# MesschieberV3.net
KiCad netlist of a schematic drawn in EAGLE
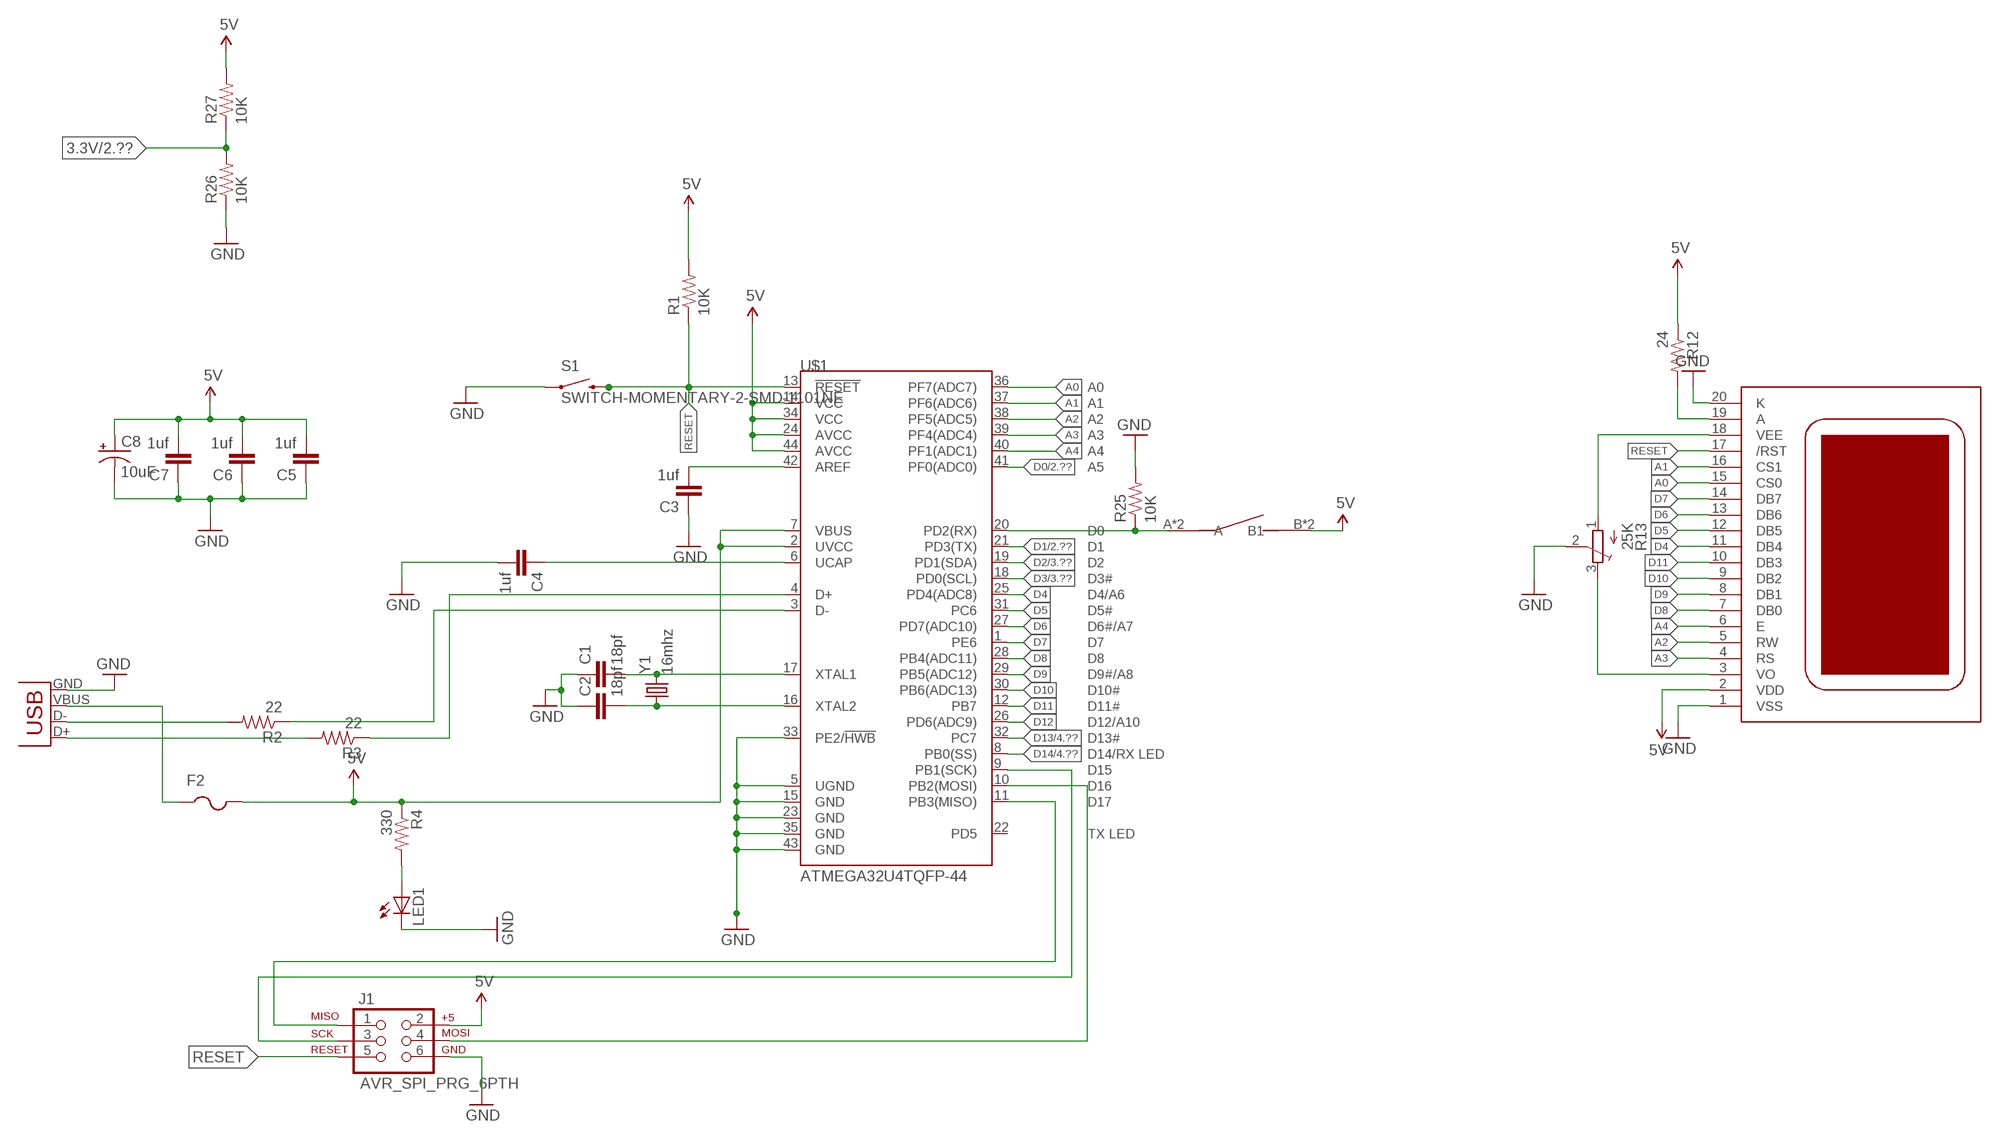
[diagram p0: schematic, sheet 1]
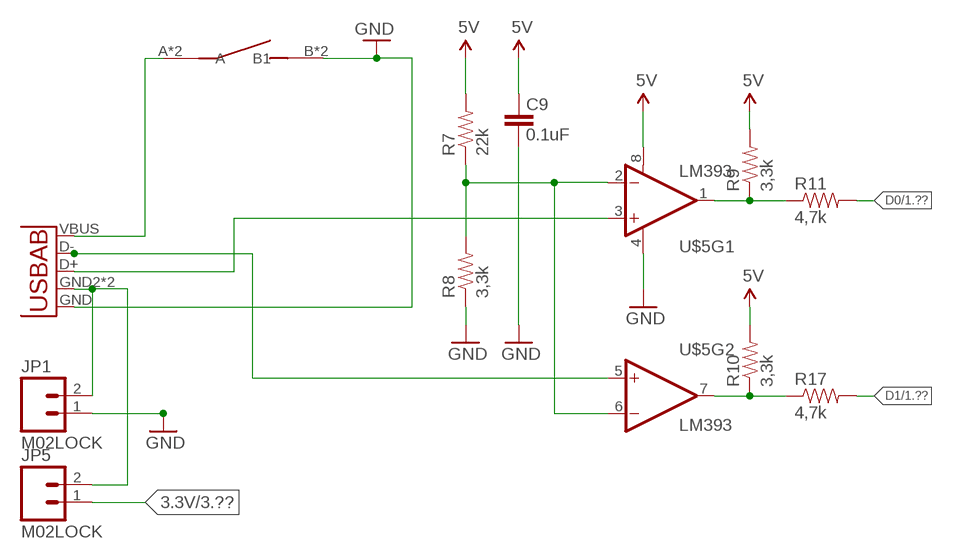
[diagram p1: schematic, sheet 2]
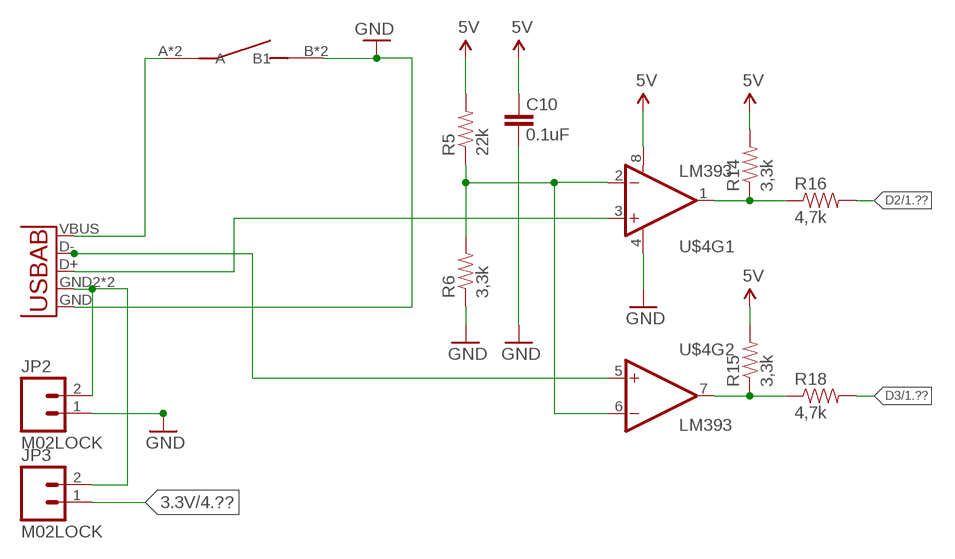
[diagram p2: schematic, sheet 3]
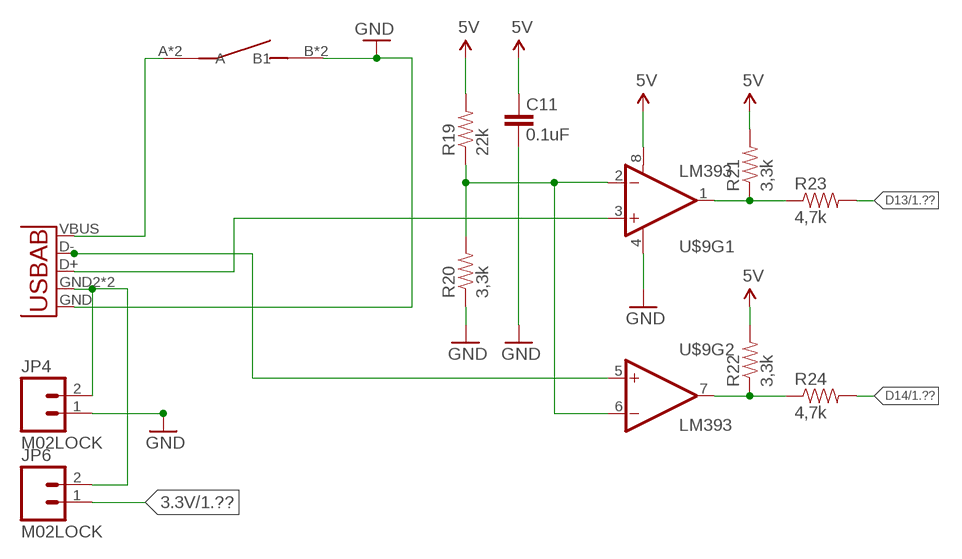
[diagram p3: schematic, sheet 4]

(export (version "E")
  (design (tool "Eeschema 10.0.6"))
  (components
    (comp (ref "C9")
      (value "0.1uF")
      (footprint "eagle-import:0805")
      (libsource (lib "eagle-import") (part "CAP0805"))
    )
    (comp (ref "JP1")
      (value "M02LOCK")
      (footprint "eagle-import:1X02_LOCK")
      (libsource (lib "eagle-import") (part "M02LOCK"))
    )
    (comp (ref "JP5")
      (value "M02LOCK")
      (footprint "eagle-import:1X02_LOCK")
      (libsource (lib "eagle-import") (part "M02LOCK"))
    )
    (comp (ref "R7")
      (value "22k")
      (footprint "eagle-import:0805")
      (libsource (lib "eagle-import") (part "RESISTOR"))
    )
    (comp (ref "R8")
      (value "3,3k")
      (footprint "eagle-import:0805")
      (libsource (lib "eagle-import") (part "RESISTOR"))
    )
    (comp (ref "R9")
      (value "3,3k")
      (footprint "eagle-import:0805")
      (libsource (lib "eagle-import") (part "RESISTOR"))
    )
    (comp (ref "R10")
      (value "3,3k")
      (footprint "eagle-import:0805")
      (libsource (lib "eagle-import") (part "RESISTOR"))
    )
    (comp (ref "R11")
      (value "4,7k")
      (footprint "eagle-import:0805")
      (libsource (lib "eagle-import") (part "RESISTOR"))
    )
    (comp (ref "R17")
      (value "4,7k")
      (footprint "eagle-import:0805")
      (libsource (lib "eagle-import") (part "RESISTOR"))
    )
    (comp (ref "U$3")
      (value "TASTE_R3FTL6")
      (footprint "eagle-import:TASTE_R3FTL6")
      (libsource (lib "eagle-import") (part "TASTE_R3FTL6"))
    )
    (comp (ref "U$5")
      (value "LM393")
      (footprint "eagle-import:SO08")
      (libsource (lib "eagle-import") (part "LM393"))
    )
    (comp (ref "U$7")
      (value "USB-A")
      (footprint "eagle-import:USB-A")
      (libsource (lib "eagle-import") (part "USB-A"))
    )
    (comp (ref "C11")
      (value "0.1uF")
      (footprint "eagle-import:0805")
      (libsource (lib "eagle-import") (part "CAP0805"))
    )
    (comp (ref "JP4")
      (value "M02LOCK")
      (footprint "eagle-import:1X02_LOCK")
      (libsource (lib "eagle-import") (part "M02LOCK"))
    )
    (comp (ref "JP6")
      (value "M02LOCK")
      (footprint "eagle-import:1X02_LOCK")
      (libsource (lib "eagle-import") (part "M02LOCK"))
    )
    (comp (ref "R19")
      (value "22k")
      (footprint "eagle-import:0805")
      (libsource (lib "eagle-import") (part "RESISTOR"))
    )
    (comp (ref "R20")
      (value "3,3k")
      (footprint "eagle-import:0805")
      (libsource (lib "eagle-import") (part "RESISTOR"))
    )
    (comp (ref "R21")
      (value "3,3k")
      (footprint "eagle-import:0805")
      (libsource (lib "eagle-import") (part "RESISTOR"))
    )
    (comp (ref "R22")
      (value "3,3k")
      (footprint "eagle-import:0805")
      (libsource (lib "eagle-import") (part "RESISTOR"))
    )
    (comp (ref "R23")
      (value "4,7k")
      (footprint "eagle-import:0805")
      (libsource (lib "eagle-import") (part "RESISTOR"))
    )
    (comp (ref "R24")
      (value "4,7k")
      (footprint "eagle-import:0805")
      (libsource (lib "eagle-import") (part "RESISTOR"))
    )
    (comp (ref "U$9")
      (value "LM393")
      (footprint "eagle-import:SO08")
      (libsource (lib "eagle-import") (part "LM393"))
    )
    (comp (ref "U$10")
      (value "USB-A")
      (footprint "eagle-import:USB-A")
      (libsource (lib "eagle-import") (part "USB-A"))
    )
    (comp (ref "U$11")
      (value "TASTE_R3FTL6")
      (footprint "eagle-import:TASTE_R3FTL6")
      (libsource (lib "eagle-import") (part "TASTE_R3FTL6"))
    )
    (comp (ref "C10")
      (value "0.1uF")
      (footprint "eagle-import:0805")
      (libsource (lib "eagle-import") (part "CAP0805"))
    )
    (comp (ref "JP2")
      (value "M02LOCK")
      (footprint "eagle-import:1X02_LOCK")
      (libsource (lib "eagle-import") (part "M02LOCK"))
    )
    (comp (ref "JP3")
      (value "M02LOCK")
      (footprint "eagle-import:1X02_LOCK")
      (libsource (lib "eagle-import") (part "M02LOCK"))
    )
    (comp (ref "R5")
      (value "22k")
      (footprint "eagle-import:0805")
      (libsource (lib "eagle-import") (part "RESISTOR"))
    )
    (comp (ref "R6")
      (value "3,3k")
      (footprint "eagle-import:0805")
      (libsource (lib "eagle-import") (part "RESISTOR"))
    )
    (comp (ref "R14")
      (value "3,3k")
      (footprint "eagle-import:0805")
      (libsource (lib "eagle-import") (part "RESISTOR"))
    )
    (comp (ref "R15")
      (value "3,3k")
      (footprint "eagle-import:0805")
      (libsource (lib "eagle-import") (part "RESISTOR"))
    )
    (comp (ref "R16")
      (value "4,7k")
      (footprint "eagle-import:0805")
      (libsource (lib "eagle-import") (part "RESISTOR"))
    )
    (comp (ref "R18")
      (value "4,7k")
      (footprint "eagle-import:0805")
      (libsource (lib "eagle-import") (part "RESISTOR"))
    )
    (comp (ref "U$4")
      (value "LM393")
      (footprint "eagle-import:SO08")
      (libsource (lib "eagle-import") (part "LM393"))
    )
    (comp (ref "U$6")
      (value "USB-A")
      (footprint "eagle-import:USB-A")
      (libsource (lib "eagle-import") (part "USB-A"))
    )
    (comp (ref "U$8")
      (value "TASTE_R3FTL6")
      (footprint "eagle-import:TASTE_R3FTL6")
      (libsource (lib "eagle-import") (part "TASTE_R3FTL6"))
    )
    (comp (ref "C1")
      (value "18pf")
      (footprint "eagle-import:0805")
      (libsource (lib "eagle-import") (part "SparkFun-Capacitors_CAP0805"))
    )
    (comp (ref "C2")
      (value "18pf")
      (footprint "eagle-import:0805")
      (libsource (lib "eagle-import") (part "SparkFun-Capacitors_CAP0805"))
    )
    (comp (ref "C3")
      (value "1uf")
      (footprint "eagle-import:0805")
      (libsource (lib "eagle-import") (part "SparkFun-Capacitors_CAP0805"))
    )
    (comp (ref "C4")
      (value "1uf")
      (footprint "eagle-import:0805")
      (libsource (lib "eagle-import") (part "SparkFun-Capacitors_CAP0805"))
    )
    (comp (ref "C5")
      (value "1uf")
      (footprint "eagle-import:0805")
      (libsource (lib "eagle-import") (part "SparkFun-Capacitors_CAP0805"))
    )
    (comp (ref "C6")
      (value "1uf")
      (footprint "eagle-import:0805")
      (libsource (lib "eagle-import") (part "SparkFun-Capacitors_CAP0805"))
    )
    (comp (ref "C7")
      (value "1uf")
      (footprint "eagle-import:0805")
      (libsource (lib "eagle-import") (part "SparkFun-Capacitors_CAP0805"))
    )
    (comp (ref "C8")
      (value "10uF")
      (footprint "eagle-import:EIA3528")
      (libsource (lib "eagle-import") (part "10UF-20V-10%(TANT)"))
    )
    (comp (ref "F2")
      (value "PTCFUSE-1812")
      (footprint "eagle-import:1812")
      (libsource (lib "eagle-import") (part "PTCFUSE-1812"))
    )
    (comp (ref "J1")
      (value "AVR_SPI_PRG_6PTH")
      (footprint "eagle-import:2X3")
      (libsource (lib "eagle-import") (part "AVR_SPI_PRG_6PTH"))
    )
    (comp (ref "JP7")
      (value "USB-SMD-NS")
      (footprint "eagle-import:USB-MINIB-NOSTOP")
      (libsource (lib "eagle-import") (part "USB-SMD-NS"))
    )
    (comp (ref "LED1")
      (value "LEDSML0805")
      (footprint "eagle-import:SML0805")
      (libsource (lib "eagle-import") (part "LEDSML0805"))
    )
    (comp (ref "R1")
      (value "10K")
      (footprint "eagle-import:0805")
      (libsource (lib "eagle-import") (part "RESISTOR"))
    )
    (comp (ref "R2")
      (value "22")
      (footprint "eagle-import:0805")
      (libsource (lib "eagle-import") (part "RESISTOR"))
    )
    (comp (ref "R3")
      (value "22")
      (footprint "eagle-import:0805")
      (libsource (lib "eagle-import") (part "RESISTOR"))
    )
    (comp (ref "R4")
      (value "330")
      (footprint "eagle-import:0805")
      (libsource (lib "eagle-import") (part "RESISTOR"))
    )
    (comp (ref "R12")
      (value "24")
      (footprint "eagle-import:0805")
      (libsource (lib "eagle-import") (part "RESISTOR"))
    )
    (comp (ref "R13")
      (value "25K")
      (footprint "eagle-import:SM-42_43A")
      (libsource (lib "eagle-import") (part "TRIM_EU-SM-42/43A"))
    )
    (comp (ref "R25")
      (value "10K")
      (footprint "eagle-import:0805")
      (libsource (lib "eagle-import") (part "RESISTOR"))
    )
    (comp (ref "R26")
      (value "10K")
      (footprint "eagle-import:0805")
      (libsource (lib "eagle-import") (part "RESISTOR"))
    )
    (comp (ref "R27")
      (value "10K")
      (footprint "eagle-import:0805")
      (libsource (lib "eagle-import") (part "RESISTOR"))
    )
    (comp (ref "S1")
      (value "SWITCH-MOMENTARY-2-SMD-1101NE")
      (footprint "eagle-import:TACTILE-SWITCH-1101NE")
      (libsource (lib "eagle-import") (part "SWITCH-MOMENTARY-2-SMD-1101NE"))
    )
    (comp (ref "U$1")
      (value "ATMEGA32U4TQFP-44")
      (footprint "eagle-import:TQFP44")
      (libsource (lib "eagle-import") (part "ATMEGA32U4TQFP-44"))
    )
    (comp (ref "U$2")
      (value "TS12864A")
      (footprint "eagle-import:TS12864")
      (libsource (lib "eagle-import") (part "TS12864A"))
    )
    (comp (ref "U$12")
      (value "TASTE_R3FTL6")
      (footprint "eagle-import:TASTE_R3FTL6")
      (libsource (lib "eagle-import") (part "TASTE_R3FTL6"))
    )
    (comp (ref "Y1")
      (value "16mhz")
      (footprint "eagle-import:CRYSTAL-SMD-5X3")
      (libsource (lib "eagle-import") (part "CRYSTAL5X3"))
    )
  )
  (nets
    (net (code "1") (name "3.3V") (class "Default")
      (node (ref "JP3") (pin "1") (pinfunction "1_1") (pintype "passive"))
      (node (ref "JP5") (pin "1") (pinfunction "1_1") (pintype "passive"))
      (node (ref "JP6") (pin "1") (pinfunction "1_1") (pintype "passive"))
      (node (ref "R26") (pin "2") (pinfunction "2_2") (pintype "passive"))
      (node (ref "R27") (pin "1") (pinfunction "1_1") (pintype "passive"))
    )
    (net (code "2") (name "5V") (class "Default")
      (node (ref "C10") (pin "2") (pinfunction "2_2") (pintype "passive"))
      (node (ref "C11") (pin "2") (pinfunction "2_2") (pintype "passive"))
      (node (ref "C5") (pin "2") (pinfunction "2_2") (pintype "passive"))
      (node (ref "C6") (pin "2") (pinfunction "2_2") (pintype "passive"))
      (node (ref "C7") (pin "2") (pinfunction "2_2") (pintype "passive"))
      (node (ref "C8") (pin "A") (pinfunction "+_A") (pintype "passive"))
      (node (ref "C9") (pin "2") (pinfunction "2_2") (pintype "passive"))
      (node (ref "F2") (pin "2") (pinfunction "2_2") (pintype "passive"))
      (node (ref "J1") (pin "2") (pinfunction "2_2") (pintype "passive"))
      (node (ref "R1") (pin "2") (pinfunction "2_2") (pintype "passive"))
      (node (ref "R10") (pin "2") (pinfunction "2_2") (pintype "passive"))
      (node (ref "R12") (pin "1") (pinfunction "1_1") (pintype "passive"))
      (node (ref "R14") (pin "2") (pinfunction "2_2") (pintype "passive"))
      (node (ref "R15") (pin "2") (pinfunction "2_2") (pintype "passive"))
      (node (ref "R19") (pin "2") (pinfunction "2_2") (pintype "passive"))
      (node (ref "R21") (pin "2") (pinfunction "2_2") (pintype "passive"))
      (node (ref "R22") (pin "2") (pinfunction "2_2") (pintype "passive"))
      (node (ref "R27") (pin "2") (pinfunction "2_2") (pintype "passive"))
      (node (ref "R4") (pin "1") (pinfunction "1_1") (pintype "passive"))
      (node (ref "R5") (pin "2") (pinfunction "2_2") (pintype "passive"))
      (node (ref "R7") (pin "2") (pinfunction "2_2") (pintype "passive"))
      (node (ref "R9") (pin "2") (pinfunction "2_2") (pintype "passive"))
      (node (ref "U$1") (pin "14") (pinfunction "VCC_14") (pintype "bidirectional"))
      (node (ref "U$1") (pin "2") (pinfunction "UVCC_2") (pintype "bidirectional"))
      (node (ref "U$1") (pin "24") (pinfunction "AVCC_24") (pintype "bidirectional"))
      (node (ref "U$1") (pin "34") (pinfunction "VCC_34") (pintype "bidirectional"))
      (node (ref "U$1") (pin "44") (pinfunction "AVCC_44") (pintype "bidirectional"))
      (node (ref "U$1") (pin "7") (pinfunction "VBUS_7") (pintype "bidirectional"))
      (node (ref "U$12") (pin "B") (pinfunction "B1_B") (pintype "bidirectional"))
      (node (ref "U$12") (pin "B1") (pinfunction "B1_B1") (pintype "bidirectional"))
      (node (ref "U$2") (pin "2") (pinfunction "VDD_2") (pintype "power_in"))
      (node (ref "U$4") (pin "8") (pinfunction "V+_8") (pintype "power_in"))
      (node (ref "U$5") (pin "8") (pinfunction "V+_8") (pintype "power_in"))
      (node (ref "U$9") (pin "8") (pinfunction "V+_8") (pintype "power_in"))
    )
    (net (code "3") (name "A0") (class "Default")
      (node (ref "U$1") (pin "36") (pinfunction "PF7(ADC7)_36") (pintype "bidirectional"))
      (node (ref "U$2") (pin "15") (pinfunction "CS0_15") (pintype "input"))
    )
    (net (code "4") (name "A1") (class "Default")
      (node (ref "U$1") (pin "37") (pinfunction "PF6(ADC6)_37") (pintype "bidirectional"))
      (node (ref "U$2") (pin "16") (pinfunction "CS1_16") (pintype "input"))
    )
    (net (code "5") (name "A2") (class "Default")
      (node (ref "U$1") (pin "38") (pinfunction "PF5(ADC5)_38") (pintype "bidirectional"))
      (node (ref "U$2") (pin "5") (pinfunction "RW_5") (pintype "input"))
    )
    (net (code "6") (name "A3") (class "Default")
      (node (ref "U$1") (pin "39") (pinfunction "PF4(ADC4)_39") (pintype "bidirectional"))
      (node (ref "U$2") (pin "4") (pinfunction "RS_4") (pintype "input"))
    )
    (net (code "7") (name "A4") (class "Default")
      (node (ref "U$1") (pin "40") (pinfunction "PF1(ADC1)_40") (pintype "bidirectional"))
      (node (ref "U$2") (pin "6") (pinfunction "E_6") (pintype "input"))
    )
    (net (code "8") (name "D0") (class "Default")
      (node (ref "R11") (pin "2") (pinfunction "2_2") (pintype "passive"))
      (node (ref "U$1") (pin "41") (pinfunction "PF0(ADC0)_41") (pintype "bidirectional"))
    )
    (net (code "9") (name "D1") (class "Default")
      (node (ref "R17") (pin "2") (pinfunction "2_2") (pintype "passive"))
      (node (ref "U$1") (pin "21") (pinfunction "PD3(TX)_21") (pintype "bidirectional"))
    )
    (net (code "10") (name "D2") (class "Default")
      (node (ref "R16") (pin "2") (pinfunction "2_2") (pintype "passive"))
      (node (ref "U$1") (pin "19") (pinfunction "PD1(SDA)_19") (pintype "bidirectional"))
    )
    (net (code "11") (name "D3") (class "Default")
      (node (ref "R18") (pin "2") (pinfunction "2_2") (pintype "passive"))
      (node (ref "U$1") (pin "18") (pinfunction "PD0(SCL)_18") (pintype "bidirectional"))
    )
    (net (code "12") (name "D4") (class "Default")
      (node (ref "U$1") (pin "25") (pinfunction "PD4(ADC8)_25") (pintype "bidirectional"))
      (node (ref "U$2") (pin "11") (pinfunction "DB4_11") (pintype "bidirectional"))
    )
    (net (code "13") (name "D5") (class "Default")
      (node (ref "U$1") (pin "31") (pinfunction "PC6_31") (pintype "bidirectional"))
      (node (ref "U$2") (pin "12") (pinfunction "DB5_12") (pintype "bidirectional"))
    )
    (net (code "14") (name "D6") (class "Default")
      (node (ref "U$1") (pin "27") (pinfunction "PD7(ADC10)_27") (pintype "bidirectional"))
      (node (ref "U$2") (pin "13") (pinfunction "DB6_13") (pintype "bidirectional"))
    )
    (net (code "15") (name "D7") (class "Default")
      (node (ref "U$1") (pin "1") (pinfunction "PE6_1") (pintype "bidirectional"))
      (node (ref "U$2") (pin "14") (pinfunction "DB7_14") (pintype "bidirectional"))
    )
    (net (code "16") (name "D8") (class "Default")
      (node (ref "U$1") (pin "28") (pinfunction "PB4(ADC11)_28") (pintype "bidirectional"))
      (node (ref "U$2") (pin "7") (pinfunction "DB0_7") (pintype "bidirectional"))
    )
    (net (code "17") (name "D9") (class "Default")
      (node (ref "U$1") (pin "29") (pinfunction "PB5(ADC12)_29") (pintype "bidirectional"))
      (node (ref "U$2") (pin "8") (pinfunction "DB1_8") (pintype "bidirectional"))
    )
    (net (code "18") (name "D10") (class "Default")
      (node (ref "U$1") (pin "30") (pinfunction "PB6(ADC13)_30") (pintype "bidirectional"))
      (node (ref "U$2") (pin "9") (pinfunction "DB2_9") (pintype "bidirectional"))
    )
    (net (code "19") (name "D11") (class "Default")
      (node (ref "U$1") (pin "12") (pinfunction "PB7_12") (pintype "bidirectional"))
      (node (ref "U$2") (pin "10") (pinfunction "DB3_10") (pintype "bidirectional"))
    )
    (net (code "20") (name "D12") (class "Default")
      (node (ref "U$1") (pin "26") (pinfunction "PD6(ADC9)_26") (pintype "bidirectional"))
    )
    (net (code "21") (name "D13") (class "Default")
      (node (ref "R23") (pin "2") (pinfunction "2_2") (pintype "passive"))
      (node (ref "U$1") (pin "32") (pinfunction "PC7_32") (pintype "bidirectional"))
    )
    (net (code "22") (name "D14") (class "Default")
      (node (ref "R24") (pin "2") (pinfunction "2_2") (pintype "passive"))
      (node (ref "U$1") (pin "8") (pinfunction "PB0(SS)_8") (pintype "bidirectional"))
    )
    (net (code "23") (name "GND") (class "Default")
      (node (ref "C1") (pin "1") (pinfunction "1_1") (pintype "passive"))
      (node (ref "C10") (pin "1") (pinfunction "1_1") (pintype "passive"))
      (node (ref "C11") (pin "1") (pinfunction "1_1") (pintype "passive"))
      (node (ref "C2") (pin "1") (pinfunction "1_1") (pintype "passive"))
      (node (ref "C3") (pin "1") (pinfunction "1_1") (pintype "passive"))
      (node (ref "C4") (pin "2") (pinfunction "2_2") (pintype "passive"))
      (node (ref "C5") (pin "1") (pinfunction "1_1") (pintype "passive"))
      (node (ref "C6") (pin "1") (pinfunction "1_1") (pintype "passive"))
      (node (ref "C7") (pin "1") (pinfunction "1_1") (pintype "passive"))
      (node (ref "C8") (pin "C") (pinfunction "-_C") (pintype "passive"))
      (node (ref "C9") (pin "1") (pinfunction "1_1") (pintype "passive"))
      (node (ref "J1") (pin "6") (pinfunction "6_6") (pintype "passive"))
      (node (ref "JP1") (pin "1") (pinfunction "1_1") (pintype "passive"))
      (node (ref "JP2") (pin "1") (pinfunction "1_1") (pintype "passive"))
      (node (ref "JP4") (pin "1") (pinfunction "1_1") (pintype "passive"))
      (node (ref "JP7") (pin "GND") (pinfunction "GND_GND") (pintype "bidirectional"))
      (node (ref "LED1") (pin "C") (pinfunction "C_C") (pintype "passive"))
      (node (ref "R13") (pin "2") (pinfunction "S_2") (pintype "passive"))
      (node (ref "R20") (pin "1") (pinfunction "1_1") (pintype "passive"))
      (node (ref "R25") (pin "2") (pinfunction "2_2") (pintype "passive"))
      (node (ref "R26") (pin "1") (pinfunction "1_1") (pintype "passive"))
      (node (ref "R6") (pin "1") (pinfunction "1_1") (pintype "passive"))
      (node (ref "R8") (pin "1") (pinfunction "1_1") (pintype "passive"))
      (node (ref "S1") (pin "P$1") (pinfunction "1_P$1") (pintype "passive"))
      (node (ref "U$1") (pin "15") (pinfunction "GND_15") (pintype "bidirectional"))
      (node (ref "U$1") (pin "23") (pinfunction "GND_23") (pintype "bidirectional"))
      (node (ref "U$1") (pin "33") (pinfunction "PE2/~{HWB}_33") (pintype "bidirectional"))
      (node (ref "U$1") (pin "35") (pinfunction "GND_35") (pintype "bidirectional"))
      (node (ref "U$1") (pin "43") (pinfunction "GND_43") (pintype "bidirectional"))
      (node (ref "U$1") (pin "5") (pinfunction "UGND_5") (pintype "bidirectional"))
      (node (ref "U$10") (pin "GND") (pinfunction "GND_GND") (pintype "bidirectional"))
      (node (ref "U$11") (pin "B") (pinfunction "B1_B") (pintype "bidirectional"))
      (node (ref "U$11") (pin "B1") (pinfunction "B1_B1") (pintype "bidirectional"))
      (node (ref "U$2") (pin "1") (pinfunction "VSS_1") (pintype "power_in"))
      (node (ref "U$2") (pin "20") (pinfunction "K_20") (pintype "input"))
      (node (ref "U$3") (pin "B") (pinfunction "B1_B") (pintype "bidirectional"))
      (node (ref "U$3") (pin "B1") (pinfunction "B1_B1") (pintype "bidirectional"))
      (node (ref "U$4") (pin "4") (pinfunction "V-_4") (pintype "power_in"))
      (node (ref "U$5") (pin "4") (pinfunction "V-_4") (pintype "power_in"))
      (node (ref "U$6") (pin "GND") (pinfunction "GND_GND") (pintype "bidirectional"))
      (node (ref "U$7") (pin "GND") (pinfunction "GND_GND") (pintype "bidirectional"))
      (node (ref "U$8") (pin "B") (pinfunction "B1_B") (pintype "bidirectional"))
      (node (ref "U$8") (pin "B1") (pinfunction "B1_B1") (pintype "bidirectional"))
      (node (ref "U$9") (pin "4") (pinfunction "V-_4") (pintype "power_in"))
    )
    (net (code "24") (name "Net-(F2-Pad1)") (class "Default")
      (node (ref "F2") (pin "1") (pinfunction "1_1") (pintype "passive"))
      (node (ref "JP7") (pin "VBUS") (pinfunction "VBUS_VBUS") (pintype "bidirectional"))
    )
    (net (code "25") (name "Net-(JP1-Pad2)") (class "Default")
      (node (ref "JP1") (pin "2") (pinfunction "2_2") (pintype "passive"))
      (node (ref "JP5") (pin "2") (pinfunction "2_2") (pintype "passive"))
      (node (ref "U$7") (pin "GND2") (pinfunction "USBID_GND2") (pintype "bidirectional"))
      (node (ref "U$7") (pin "GND3") (pinfunction "USBID_GND3") (pintype "bidirectional"))
    )
    (net (code "26") (name "Net-(JP2-Pad2)") (class "Default")
      (node (ref "JP2") (pin "2") (pinfunction "2_2") (pintype "passive"))
      (node (ref "JP3") (pin "2") (pinfunction "2_2") (pintype "passive"))
      (node (ref "U$6") (pin "GND2") (pinfunction "USBID_GND2") (pintype "bidirectional"))
      (node (ref "U$6") (pin "GND3") (pinfunction "USBID_GND3") (pintype "bidirectional"))
    )
    (net (code "27") (name "Net-(JP4-Pad2)") (class "Default")
      (node (ref "JP4") (pin "2") (pinfunction "2_2") (pintype "passive"))
      (node (ref "JP6") (pin "2") (pinfunction "2_2") (pintype "passive"))
      (node (ref "U$10") (pin "GND2") (pinfunction "USBID_GND2") (pintype "bidirectional"))
      (node (ref "U$10") (pin "GND3") (pinfunction "USBID_GND3") (pintype "bidirectional"))
    )
    (net (code "28") (name "Net-(JP7-PadD+)") (class "Default")
      (node (ref "JP7") (pin "D+") (pinfunction "D+_D+") (pintype "bidirectional"))
      (node (ref "R3") (pin "2") (pinfunction "2_2") (pintype "passive"))
    )
    (net (code "29") (name "Net-(JP7-PadD-)") (class "Default")
      (node (ref "JP7") (pin "D-") (pinfunction "D-_D-") (pintype "bidirectional"))
      (node (ref "R2") (pin "2") (pinfunction "2_2") (pintype "passive"))
    )
    (net (code "30") (name "Net-(LED1-PadA)") (class "Default")
      (node (ref "LED1") (pin "A") (pinfunction "A_A") (pintype "passive"))
      (node (ref "R4") (pin "2") (pinfunction "2_2") (pintype "passive"))
    )
    (net (code "31") (name "Net-(R13-A)") (class "Default")
      (node (ref "R13") (pin "1") (pinfunction "A_1") (pintype "passive"))
      (node (ref "U$2") (pin "18") (pinfunction "VEE_18") (pintype "power_in"))
    )
    (net (code "32") (name "Net-(R13-E)") (class "Default")
      (node (ref "R13") (pin "3") (pinfunction "E_3") (pintype "passive"))
      (node (ref "U$2") (pin "3") (pinfunction "VO_3") (pintype "input"))
    )
    (net (code "33") (name "Net-(U$1-AREF)") (class "Default")
      (node (ref "C3") (pin "2") (pinfunction "2_2") (pintype "passive"))
      (node (ref "U$1") (pin "42") (pinfunction "AREF_42") (pintype "bidirectional"))
    )
    (net (code "34") (name "Net-(U$1-D+)") (class "Default")
      (node (ref "R3") (pin "1") (pinfunction "1_1") (pintype "passive"))
      (node (ref "U$1") (pin "4") (pinfunction "D+_4") (pintype "bidirectional"))
    )
    (net (code "35") (name "Net-(U$1-D-)") (class "Default")
      (node (ref "R2") (pin "1") (pinfunction "1_1") (pintype "passive"))
      (node (ref "U$1") (pin "3") (pinfunction "D-_3") (pintype "bidirectional"))
    )
    (net (code "36") (name "Net-(U$1-PB1(SCK))") (class "Default")
      (node (ref "J1") (pin "3") (pinfunction "3_3") (pintype "passive"))
      (node (ref "U$1") (pin "9") (pinfunction "PB1(SCK)_9") (pintype "bidirectional"))
    )
    (net (code "37") (name "Net-(U$1-PB2(MOSI))") (class "Default")
      (node (ref "J1") (pin "4") (pinfunction "4_4") (pintype "passive"))
      (node (ref "U$1") (pin "10") (pinfunction "PB2(MOSI)_10") (pintype "bidirectional"))
    )
    (net (code "38") (name "Net-(U$1-PB3(MISO))") (class "Default")
      (node (ref "J1") (pin "1") (pinfunction "1_1") (pintype "passive"))
      (node (ref "U$1") (pin "11") (pinfunction "PB3(MISO)_11") (pintype "bidirectional"))
    )
    (net (code "39") (name "Net-(U$1-PD2(RX))") (class "Default")
      (node (ref "R25") (pin "1") (pinfunction "1_1") (pintype "passive"))
      (node (ref "U$1") (pin "20") (pinfunction "PD2(RX)_20") (pintype "bidirectional"))
      (node (ref "U$12") (pin "A") (pinfunction "A_A") (pintype "bidirectional"))
      (node (ref "U$12") (pin "A1") (pinfunction "A_A1") (pintype "bidirectional"))
    )
    (net (code "40") (name "Net-(U$1-UCAP)") (class "Default")
      (node (ref "C4") (pin "1") (pinfunction "1_1") (pintype "passive"))
      (node (ref "U$1") (pin "6") (pinfunction "UCAP_6") (pintype "bidirectional"))
    )
    (net (code "41") (name "Net-(U$1-XTAL1)") (class "Default")
      (node (ref "C1") (pin "2") (pinfunction "2_2") (pintype "passive"))
      (node (ref "U$1") (pin "17") (pinfunction "XTAL1_17") (pintype "bidirectional"))
      (node (ref "Y1") (pin "3") (pinfunction "2_3") (pintype "passive"))
    )
    (net (code "42") (name "Net-(U$1-XTAL2)") (class "Default")
      (node (ref "C2") (pin "2") (pinfunction "2_2") (pintype "passive"))
      (node (ref "U$1") (pin "16") (pinfunction "XTAL2_16") (pintype "bidirectional"))
      (node (ref "Y1") (pin "1") (pinfunction "1_1") (pintype "passive"))
    )
    (net (code "43") (name "Net-(U$2-A)") (class "Default")
      (node (ref "R12") (pin "2") (pinfunction "2_2") (pintype "passive"))
      (node (ref "U$2") (pin "19") (pinfunction "A_19") (pintype "power_in"))
    )
    (net (code "44") (name "Net-(U$3-A-PadA1)") (class "Default")
      (node (ref "U$3") (pin "A") (pinfunction "A_A") (pintype "bidirectional"))
      (node (ref "U$3") (pin "A1") (pinfunction "A_A1") (pintype "bidirectional"))
      (node (ref "U$7") (pin "VBUS") (pinfunction "VBUS_VBUS") (pintype "bidirectional"))
    )
    (net (code "45") (name "Net-(U$4A-+IN)") (class "Default")
      (node (ref "U$4") (pin "3") (pinfunction "+IN_3") (pintype "input"))
      (node (ref "U$6") (pin "D+") (pinfunction "D+_D+") (pintype "bidirectional"))
    )
    (net (code "46") (name "Net-(U$4A--IN)") (class "Default")
      (node (ref "R5") (pin "1") (pinfunction "1_1") (pintype "passive"))
      (node (ref "R6") (pin "2") (pinfunction "2_2") (pintype "passive"))
      (node (ref "U$4") (pin "2") (pinfunction "-IN_2") (pintype "input"))
      (node (ref "U$4") (pin "6") (pinfunction "-IN_6") (pintype "input"))
    )
    (net (code "47") (name "Net-(U$4A-OUT)") (class "Default")
      (node (ref "R14") (pin "1") (pinfunction "1_1") (pintype "passive"))
      (node (ref "R16") (pin "1") (pinfunction "1_1") (pintype "passive"))
      (node (ref "U$4") (pin "1") (pinfunction "OUT_1") (pintype "output"))
    )
    (net (code "48") (name "Net-(U$4B-+IN)") (class "Default")
      (node (ref "U$4") (pin "5") (pinfunction "+IN_5") (pintype "input"))
      (node (ref "U$6") (pin "D-") (pinfunction "D-_D-") (pintype "bidirectional"))
    )
    (net (code "49") (name "Net-(U$4B-OUT)") (class "Default")
      (node (ref "R15") (pin "1") (pinfunction "1_1") (pintype "passive"))
      (node (ref "R18") (pin "1") (pinfunction "1_1") (pintype "passive"))
      (node (ref "U$4") (pin "7") (pinfunction "OUT_7") (pintype "output"))
    )
    (net (code "50") (name "Net-(U$5A-+IN)") (class "Default")
      (node (ref "U$5") (pin "3") (pinfunction "+IN_3") (pintype "input"))
      (node (ref "U$7") (pin "D+") (pinfunction "D+_D+") (pintype "bidirectional"))
    )
    (net (code "51") (name "Net-(U$5A--IN)") (class "Default")
      (node (ref "R7") (pin "1") (pinfunction "1_1") (pintype "passive"))
      (node (ref "R8") (pin "2") (pinfunction "2_2") (pintype "passive"))
      (node (ref "U$5") (pin "2") (pinfunction "-IN_2") (pintype "input"))
      (node (ref "U$5") (pin "6") (pinfunction "-IN_6") (pintype "input"))
    )
    (net (code "52") (name "Net-(U$5A-OUT)") (class "Default")
      (node (ref "R11") (pin "1") (pinfunction "1_1") (pintype "passive"))
      (node (ref "R9") (pin "1") (pinfunction "1_1") (pintype "passive"))
      (node (ref "U$5") (pin "1") (pinfunction "OUT_1") (pintype "output"))
    )
    (net (code "53") (name "Net-(U$5B-+IN)") (class "Default")
      (node (ref "U$5") (pin "5") (pinfunction "+IN_5") (pintype "input"))
      (node (ref "U$7") (pin "D-") (pinfunction "D-_D-") (pintype "bidirectional"))
    )
    (net (code "54") (name "Net-(U$5B-OUT)") (class "Default")
      (node (ref "R10") (pin "1") (pinfunction "1_1") (pintype "passive"))
      (node (ref "R17") (pin "1") (pinfunction "1_1") (pintype "passive"))
      (node (ref "U$5") (pin "7") (pinfunction "OUT_7") (pintype "output"))
    )
    (net (code "55") (name "Net-(U$6-PadVBUS)") (class "Default")
      (node (ref "U$6") (pin "VBUS") (pinfunction "VBUS_VBUS") (pintype "bidirectional"))
      (node (ref "U$8") (pin "A") (pinfunction "A_A") (pintype "bidirectional"))
      (node (ref "U$8") (pin "A1") (pinfunction "A_A1") (pintype "bidirectional"))
    )
    (net (code "56") (name "Net-(U$9A-+IN)") (class "Default")
      (node (ref "U$10") (pin "D+") (pinfunction "D+_D+") (pintype "bidirectional"))
      (node (ref "U$9") (pin "3") (pinfunction "+IN_3") (pintype "input"))
    )
    (net (code "57") (name "Net-(U$9A--IN)") (class "Default")
      (node (ref "R19") (pin "1") (pinfunction "1_1") (pintype "passive"))
      (node (ref "R20") (pin "2") (pinfunction "2_2") (pintype "passive"))
      (node (ref "U$9") (pin "2") (pinfunction "-IN_2") (pintype "input"))
      (node (ref "U$9") (pin "6") (pinfunction "-IN_6") (pintype "input"))
    )
    (net (code "58") (name "Net-(U$9A-OUT)") (class "Default")
      (node (ref "R21") (pin "1") (pinfunction "1_1") (pintype "passive"))
      (node (ref "R23") (pin "1") (pinfunction "1_1") (pintype "passive"))
      (node (ref "U$9") (pin "1") (pinfunction "OUT_1") (pintype "output"))
    )
    (net (code "59") (name "Net-(U$9B-+IN)") (class "Default")
      (node (ref "U$10") (pin "D-") (pinfunction "D-_D-") (pintype "bidirectional"))
      (node (ref "U$9") (pin "5") (pinfunction "+IN_5") (pintype "input"))
    )
    (net (code "60") (name "Net-(U$9B-OUT)") (class "Default")
      (node (ref "R22") (pin "1") (pinfunction "1_1") (pintype "passive"))
      (node (ref "R24") (pin "1") (pinfunction "1_1") (pintype "passive"))
      (node (ref "U$9") (pin "7") (pinfunction "OUT_7") (pintype "output"))
    )
    (net (code "61") (name "Net-(U$10-PadVBUS)") (class "Default")
      (node (ref "U$10") (pin "VBUS") (pinfunction "VBUS_VBUS") (pintype "bidirectional"))
      (node (ref "U$11") (pin "A") (pinfunction "A_A") (pintype "bidirectional"))
      (node (ref "U$11") (pin "A1") (pinfunction "A_A1") (pintype "bidirectional"))
    )
    (net (code "62") (name "RESET") (class "Default")
      (node (ref "J1") (pin "5") (pinfunction "5_5") (pintype "passive"))
      (node (ref "R1") (pin "1") (pinfunction "1_1") (pintype "passive"))
      (node (ref "S1") (pin "P$2") (pinfunction "2_P$2") (pintype "passive"))
      (node (ref "U$1") (pin "13") (pinfunction "~{RESET}_13") (pintype "bidirectional"))
      (node (ref "U$2") (pin "17") (pinfunction "/RST_17") (pintype "input"))
    )
    (net (code "63") (name "unconnected-(U$1-PD5-Pad22)") (class "Default")
      (node (ref "U$1") (pin "22") (pinfunction "PD5_22") (pintype "bidirectional"))
    )
  )
)
